# esquematico_trampa.net
KiCad netlist of a schematic drawn in EAGLE
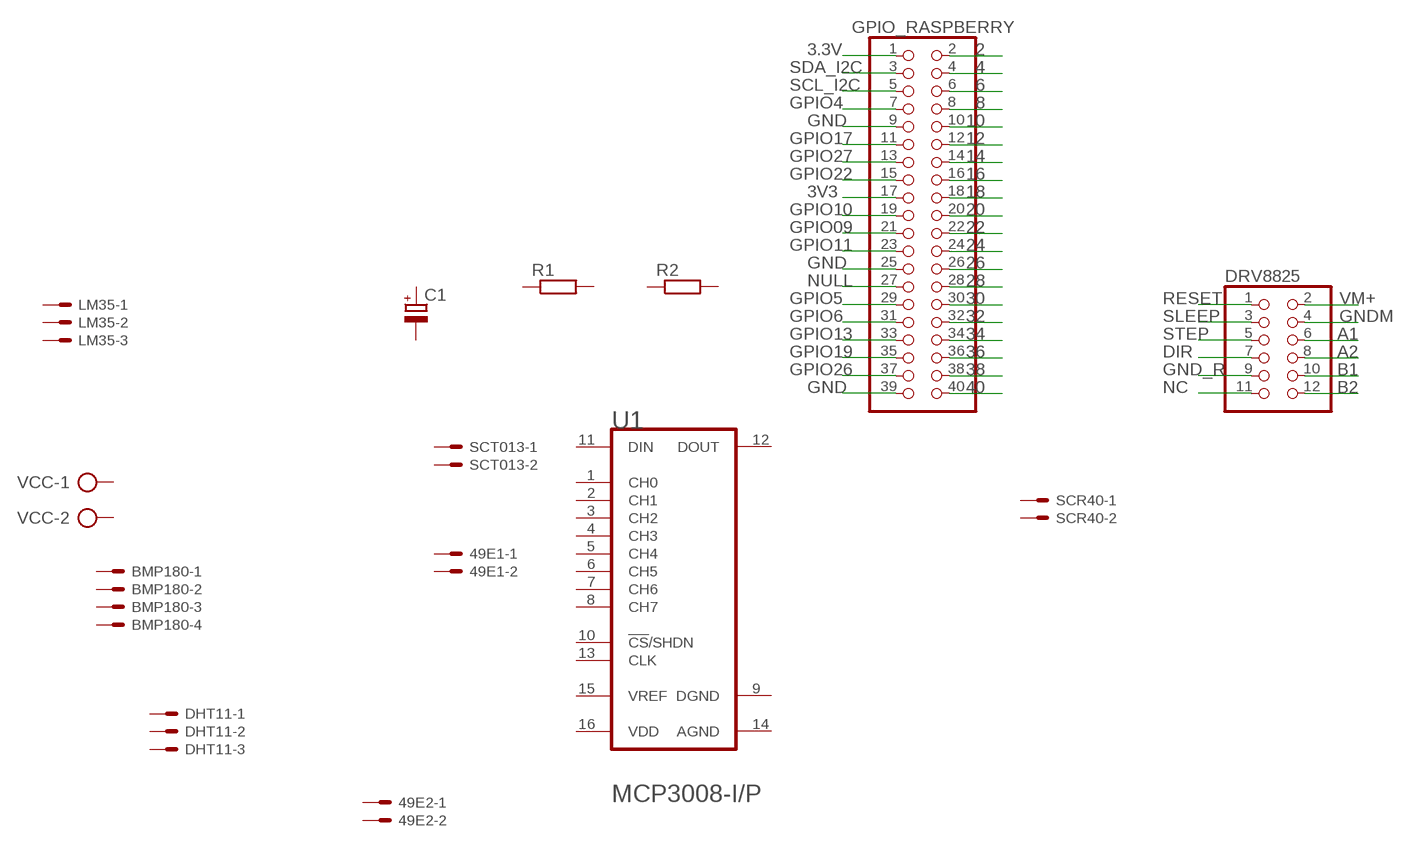
[diagram p0: schematic, sheet 1]

(export (version "E")
  (design (tool "Eeschema 10.0.6"))
  (components
    (comp (ref "49E1")
      (value "22-23-2021")
      (footprint "eagle-import:22-23-2021")
      (fields (field (name "MF") "MOLEX"))
      (libsource (lib "eagle-import") (part "22-23-2021"))
    )
    (comp (ref "49E2")
      (value "22-23-2021")
      (footprint "eagle-import:22-23-2021")
      (fields (field (name "MF") "MOLEX"))
      (libsource (lib "eagle-import") (part "22-23-2021"))
    )
    (comp (ref "BMP180")
      (value "22-23-2041")
      (footprint "eagle-import:22-23-2041")
      (fields (field (name "MF") "MOLEX"))
      (libsource (lib "eagle-import") (part "22-23-2041"))
    )
    (comp (ref "C1")
      (value "CPOL-EUE5-8.5")
      (footprint "eagle-import:E5-8,5")
      (libsource (lib "eagle-import") (part "CPOL-EUE5-8.5"))
    )
    (comp (ref "DHT11")
      (value "22-23-2031")
      (footprint "eagle-import:22-23-2031")
      (fields (field (name "MF") "MOLEX"))
      (libsource (lib "eagle-import") (part "22-23-2031"))
    )
    (comp (ref "DRV8825")
      (value "PINHD-2X6")
      (footprint "eagle-import:2X06")
      (fields (field (name "SPICEPREFIX") "X"))
      (libsource (lib "eagle-import") (part "PINHD-2X6"))
    )
    (comp (ref "GPIO_RASPBERRY")
      (value "PINHD-2X20")
      (footprint "eagle-import:2X20")
      (libsource (lib "eagle-import") (part "PINHD-2X20"))
    )
    (comp (ref "LM35")
      (value "22-23-2031")
      (footprint "eagle-import:22-23-2031")
      (fields (field (name "MF") "MOLEX"))
      (libsource (lib "eagle-import") (part "22-23-2031"))
    )
    (comp (ref "R1")
      (value "R-EU_0309/12")
      (footprint "eagle-import:0309_12")
      (libsource (lib "eagle-import") (part "R-EU_0309/12"))
    )
    (comp (ref "R2")
      (value "R-EU_0309/12")
      (footprint "eagle-import:0309_12")
      (libsource (lib "eagle-import") (part "R-EU_0309/12"))
    )
    (comp (ref "SCR40")
      (value "22-23-2021")
      (footprint "eagle-import:22-23-2021")
      (fields (field (name "MF") "MOLEX"))
      (libsource (lib "eagle-import") (part "22-23-2021"))
    )
    (comp (ref "SCT013")
      (value "22-23-2021")
      (footprint "eagle-import:22-23-2021")
      (fields (field (name "MF") "MOLEX"))
      (libsource (lib "eagle-import") (part "22-23-2021"))
    )
    (comp (ref "U1")
      (value "MICROCHIP_MCP3008-I-PMICROCHIP_MCP3008-I-P_0_0")
      (footprint "eagle-import:MICROCHIP_MCP3008-I-P_0")
      (fields (field (name "MF") "Microchip") (field (name "MPN") "MCP3008-I/P"))
      (libsource (lib "eagle-import") (part "MICROCHIP_MCP3008-I-PMICROCHIP_MCP3008-I-P_0_0"))
    )
    (comp (ref "VCC")
      (value "AK500/2-H")
      (footprint "eagle-import:AK500_2-H")
      (libsource (lib "eagle-import") (part "AK500/2-H"))
    )
  )
  (nets
    (net (code "1") (name "/2") (class "Default")
      (node (ref "GPIO_RASPBERRY") (pin "2") (pinfunction "2_2") (pintype "passive"))
    )
    (net (code "2") (name "/3.3V") (class "Default")
      (node (ref "GPIO_RASPBERRY") (pin "1") (pinfunction "1_1") (pintype "passive"))
    )
    (net (code "3") (name "/3V3") (class "Default")
      (node (ref "GPIO_RASPBERRY") (pin "17") (pinfunction "17_17") (pintype "passive"))
    )
    (net (code "4") (name "/4") (class "Default")
      (node (ref "GPIO_RASPBERRY") (pin "4") (pinfunction "4_4") (pintype "passive"))
    )
    (net (code "5") (name "/6") (class "Default")
      (node (ref "GPIO_RASPBERRY") (pin "6") (pinfunction "6_6") (pintype "passive"))
    )
    (net (code "6") (name "/8") (class "Default")
      (node (ref "GPIO_RASPBERRY") (pin "8") (pinfunction "8_8") (pintype "passive"))
    )
    (net (code "7") (name "/10") (class "Default")
      (node (ref "GPIO_RASPBERRY") (pin "10") (pinfunction "10_10") (pintype "passive"))
    )
    (net (code "8") (name "/12") (class "Default")
      (node (ref "GPIO_RASPBERRY") (pin "12") (pinfunction "12_12") (pintype "passive"))
    )
    (net (code "9") (name "/14") (class "Default")
      (node (ref "GPIO_RASPBERRY") (pin "14") (pinfunction "14_14") (pintype "passive"))
    )
    (net (code "10") (name "/16") (class "Default")
      (node (ref "GPIO_RASPBERRY") (pin "16") (pinfunction "16_16") (pintype "passive"))
    )
    (net (code "11") (name "/18") (class "Default")
      (node (ref "GPIO_RASPBERRY") (pin "18") (pinfunction "18_18") (pintype "passive"))
    )
    (net (code "12") (name "/20") (class "Default")
      (node (ref "GPIO_RASPBERRY") (pin "20") (pinfunction "20_20") (pintype "passive"))
    )
    (net (code "13") (name "/22") (class "Default")
      (node (ref "GPIO_RASPBERRY") (pin "22") (pinfunction "22_22") (pintype "passive"))
    )
    (net (code "14") (name "/24") (class "Default")
      (node (ref "GPIO_RASPBERRY") (pin "24") (pinfunction "24_24") (pintype "passive"))
    )
    (net (code "15") (name "/26") (class "Default")
      (node (ref "GPIO_RASPBERRY") (pin "26") (pinfunction "26_26") (pintype "passive"))
    )
    (net (code "16") (name "/28") (class "Default")
      (node (ref "GPIO_RASPBERRY") (pin "28") (pinfunction "28_28") (pintype "passive"))
    )
    (net (code "17") (name "/30") (class "Default")
      (node (ref "GPIO_RASPBERRY") (pin "30") (pinfunction "30_30") (pintype "passive"))
    )
    (net (code "18") (name "/32") (class "Default")
      (node (ref "GPIO_RASPBERRY") (pin "32") (pinfunction "32_32") (pintype "passive"))
    )
    (net (code "19") (name "/34") (class "Default")
      (node (ref "GPIO_RASPBERRY") (pin "34") (pinfunction "34_34") (pintype "passive"))
    )
    (net (code "20") (name "/36") (class "Default")
      (node (ref "GPIO_RASPBERRY") (pin "36") (pinfunction "36_36") (pintype "passive"))
    )
    (net (code "21") (name "/38") (class "Default")
      (node (ref "GPIO_RASPBERRY") (pin "38") (pinfunction "38_38") (pintype "passive"))
    )
    (net (code "22") (name "/40") (class "Default")
      (node (ref "GPIO_RASPBERRY") (pin "40") (pinfunction "40_40") (pintype "passive"))
    )
    (net (code "23") (name "/A1") (class "Default")
      (node (ref "DRV8825") (pin "6") (pinfunction "6_6") (pintype "passive"))
    )
    (net (code "24") (name "/A2") (class "Default")
      (node (ref "DRV8825") (pin "8") (pinfunction "8_8") (pintype "passive"))
    )
    (net (code "25") (name "/AGND") (class "Default")
      (node (ref "U1") (pin "14") (pinfunction "AGND_14") (pintype "power_in"))
    )
    (net (code "26") (name "/B1") (class "Default")
      (node (ref "DRV8825") (pin "10") (pinfunction "10_10") (pintype "passive"))
    )
    (net (code "27") (name "/B2") (class "Default")
      (node (ref "DRV8825") (pin "12") (pinfunction "12_12") (pintype "passive"))
    )
    (net (code "28") (name "/DGND") (class "Default")
      (node (ref "U1") (pin "9") (pinfunction "DGND_9") (pintype "power_in"))
    )
    (net (code "29") (name "/DIR") (class "Default")
      (node (ref "DRV8825") (pin "7") (pinfunction "7_7") (pintype "passive"))
    )
    (net (code "30") (name "/GND") (class "Default")
      (node (ref "GPIO_RASPBERRY") (pin "25") (pinfunction "25_25") (pintype "passive"))
      (node (ref "GPIO_RASPBERRY") (pin "39") (pinfunction "39_39") (pintype "passive"))
      (node (ref "GPIO_RASPBERRY") (pin "9") (pinfunction "9_9") (pintype "passive"))
    )
    (net (code "31") (name "/GNDM") (class "Default")
      (node (ref "DRV8825") (pin "4") (pinfunction "4_4") (pintype "passive"))
    )
    (net (code "32") (name "/GND_R") (class "Default")
      (node (ref "DRV8825") (pin "9") (pinfunction "9_9") (pintype "passive"))
    )
    (net (code "33") (name "/GPIO4") (class "Default")
      (node (ref "GPIO_RASPBERRY") (pin "7") (pinfunction "7_7") (pintype "passive"))
    )
    (net (code "34") (name "/GPIO5") (class "Default")
      (node (ref "GPIO_RASPBERRY") (pin "29") (pinfunction "29_29") (pintype "passive"))
    )
    (net (code "35") (name "/GPIO6") (class "Default")
      (node (ref "GPIO_RASPBERRY") (pin "31") (pinfunction "31_31") (pintype "passive"))
    )
    (net (code "36") (name "/GPIO09") (class "Default")
      (node (ref "GPIO_RASPBERRY") (pin "21") (pinfunction "21_21") (pintype "passive"))
    )
    (net (code "37") (name "/GPIO10") (class "Default")
      (node (ref "GPIO_RASPBERRY") (pin "19") (pinfunction "19_19") (pintype "passive"))
    )
    (net (code "38") (name "/GPIO11") (class "Default")
      (node (ref "GPIO_RASPBERRY") (pin "23") (pinfunction "23_23") (pintype "passive"))
    )
    (net (code "39") (name "/GPIO13") (class "Default")
      (node (ref "GPIO_RASPBERRY") (pin "33") (pinfunction "33_33") (pintype "passive"))
    )
    (net (code "40") (name "/GPIO17") (class "Default")
      (node (ref "GPIO_RASPBERRY") (pin "11") (pinfunction "11_11") (pintype "passive"))
    )
    (net (code "41") (name "/GPIO19") (class "Default")
      (node (ref "GPIO_RASPBERRY") (pin "35") (pinfunction "35_35") (pintype "passive"))
    )
    (net (code "42") (name "/GPIO22") (class "Default")
      (node (ref "GPIO_RASPBERRY") (pin "15") (pinfunction "15_15") (pintype "passive"))
    )
    (net (code "43") (name "/GPIO26") (class "Default")
      (node (ref "GPIO_RASPBERRY") (pin "37") (pinfunction "37_37") (pintype "passive"))
    )
    (net (code "44") (name "/GPIO27") (class "Default")
      (node (ref "GPIO_RASPBERRY") (pin "13") (pinfunction "13_13") (pintype "passive"))
    )
    (net (code "45") (name "/NC") (class "Default")
      (node (ref "DRV8825") (pin "11") (pinfunction "11_11") (pintype "passive"))
    )
    (net (code "46") (name "/NULL") (class "Default")
      (node (ref "GPIO_RASPBERRY") (pin "27") (pinfunction "27_27") (pintype "passive"))
    )
    (net (code "47") (name "/RESET") (class "Default")
      (node (ref "DRV8825") (pin "1") (pinfunction "1_1") (pintype "passive"))
    )
    (net (code "48") (name "/SCL_I2C") (class "Default")
      (node (ref "GPIO_RASPBERRY") (pin "5") (pinfunction "5_5") (pintype "passive"))
    )
    (net (code "49") (name "/SDA_I2C") (class "Default")
      (node (ref "GPIO_RASPBERRY") (pin "3") (pinfunction "3_3") (pintype "passive"))
    )
    (net (code "50") (name "/SLEEP") (class "Default")
      (node (ref "DRV8825") (pin "3") (pinfunction "3_3") (pintype "passive"))
    )
    (net (code "51") (name "/STEP") (class "Default")
      (node (ref "DRV8825") (pin "5") (pinfunction "5_5") (pintype "passive"))
    )
    (net (code "52") (name "/VDD") (class "Default")
      (node (ref "U1") (pin "16") (pinfunction "VDD_16") (pintype "power_in"))
    )
    (net (code "53") (name "/VM+") (class "Default")
      (node (ref "DRV8825") (pin "2") (pinfunction "2_2") (pintype "passive"))
    )
    (net (code "54") (name "unconnected-(49E1A-S-Pad1)") (class "Default")
      (node (ref "49E1") (pin "1") (pinfunction "S_1") (pintype "passive"))
    )
    (net (code "55") (name "unconnected-(49E1B-S-Pad2)") (class "Default")
      (node (ref "49E1") (pin "2") (pinfunction "S_2") (pintype "passive"))
    )
    (net (code "56") (name "unconnected-(49E2A-S-Pad1)") (class "Default")
      (node (ref "49E2") (pin "1") (pinfunction "S_1") (pintype "passive"))
    )
    (net (code "57") (name "unconnected-(49E2B-S-Pad2)") (class "Default")
      (node (ref "49E2") (pin "2") (pinfunction "S_2") (pintype "passive"))
    )
    (net (code "58") (name "unconnected-(BMP180A-S-Pad1)") (class "Default")
      (node (ref "BMP180") (pin "1") (pinfunction "S_1") (pintype "passive"))
    )
    (net (code "59") (name "unconnected-(BMP180B-S-Pad2)") (class "Default")
      (node (ref "BMP180") (pin "2") (pinfunction "S_2") (pintype "passive"))
    )
    (net (code "60") (name "unconnected-(BMP180C-S-Pad3)") (class "Default")
      (node (ref "BMP180") (pin "3") (pinfunction "S_3") (pintype "passive"))
    )
    (net (code "61") (name "unconnected-(BMP180D-S-Pad4)") (class "Default")
      (node (ref "BMP180") (pin "4") (pinfunction "S_4") (pintype "passive"))
    )
    (net (code "62") (name "unconnected-(C1-Pad+)") (class "Default")
      (node (ref "C1") (pin "+") (pinfunction "+_+") (pintype "passive"))
    )
    (net (code "63") (name "unconnected-(C1-Pad-)") (class "Default")
      (node (ref "C1") (pin "-") (pinfunction "-_-") (pintype "passive"))
    )
    (net (code "64") (name "unconnected-(DHT11A-S-Pad1)") (class "Default")
      (node (ref "DHT11") (pin "1") (pinfunction "S_1") (pintype "passive"))
    )
    (net (code "65") (name "unconnected-(DHT11B-S-Pad2)") (class "Default")
      (node (ref "DHT11") (pin "2") (pinfunction "S_2") (pintype "passive"))
    )
    (net (code "66") (name "unconnected-(DHT11C-S-Pad3)") (class "Default")
      (node (ref "DHT11") (pin "3") (pinfunction "S_3") (pintype "passive"))
    )
    (net (code "67") (name "unconnected-(LM35A-S-Pad1)") (class "Default")
      (node (ref "LM35") (pin "1") (pinfunction "S_1") (pintype "passive"))
    )
    (net (code "68") (name "unconnected-(LM35B-S-Pad2)") (class "Default")
      (node (ref "LM35") (pin "2") (pinfunction "S_2") (pintype "passive"))
    )
    (net (code "69") (name "unconnected-(LM35C-S-Pad3)") (class "Default")
      (node (ref "LM35") (pin "3") (pinfunction "S_3") (pintype "passive"))
    )
    (net (code "70") (name "unconnected-(R1-Pad1)") (class "Default")
      (node (ref "R1") (pin "1") (pinfunction "1_1") (pintype "passive"))
    )
    (net (code "71") (name "unconnected-(R1-Pad2)") (class "Default")
      (node (ref "R1") (pin "2") (pinfunction "2_2") (pintype "passive"))
    )
    (net (code "72") (name "unconnected-(R2-Pad1)") (class "Default")
      (node (ref "R2") (pin "1") (pinfunction "1_1") (pintype "passive"))
    )
    (net (code "73") (name "unconnected-(R2-Pad2)") (class "Default")
      (node (ref "R2") (pin "2") (pinfunction "2_2") (pintype "passive"))
    )
    (net (code "74") (name "unconnected-(SCR40A-S-Pad1)") (class "Default")
      (node (ref "SCR40") (pin "1") (pinfunction "S_1") (pintype "passive"))
    )
    (net (code "75") (name "unconnected-(SCR40B-S-Pad2)") (class "Default")
      (node (ref "SCR40") (pin "2") (pinfunction "S_2") (pintype "passive"))
    )
    (net (code "76") (name "unconnected-(SCT013A-S-Pad1)") (class "Default")
      (node (ref "SCT013") (pin "1") (pinfunction "S_1") (pintype "passive"))
    )
    (net (code "77") (name "unconnected-(SCT013B-S-Pad2)") (class "Default")
      (node (ref "SCT013") (pin "2") (pinfunction "S_2") (pintype "passive"))
    )
    (net (code "78") (name "unconnected-(U1-CH0-Pad1)") (class "Default")
      (node (ref "U1") (pin "1") (pinfunction "CH0_1") (pintype "input"))
    )
    (net (code "79") (name "unconnected-(U1-CH1-Pad2)") (class "Default")
      (node (ref "U1") (pin "2") (pinfunction "CH1_2") (pintype "input"))
    )
    (net (code "80") (name "unconnected-(U1-CH2-Pad3)") (class "Default")
      (node (ref "U1") (pin "3") (pinfunction "CH2_3") (pintype "input"))
    )
    (net (code "81") (name "unconnected-(U1-CH3-Pad4)") (class "Default")
      (node (ref "U1") (pin "4") (pinfunction "CH3_4") (pintype "input"))
    )
    (net (code "82") (name "unconnected-(U1-CH4-Pad5)") (class "Default")
      (node (ref "U1") (pin "5") (pinfunction "CH4_5") (pintype "input"))
    )
    (net (code "83") (name "unconnected-(U1-CH5-Pad6)") (class "Default")
      (node (ref "U1") (pin "6") (pinfunction "CH5_6") (pintype "input"))
    )
    (net (code "84") (name "unconnected-(U1-CH6-Pad7)") (class "Default")
      (node (ref "U1") (pin "7") (pinfunction "CH6_7") (pintype "input"))
    )
    (net (code "85") (name "unconnected-(U1-CH7-Pad8)") (class "Default")
      (node (ref "U1") (pin "8") (pinfunction "CH7_8") (pintype "input"))
    )
    (net (code "86") (name "unconnected-(U1-CLK-Pad13)") (class "Default")
      (node (ref "U1") (pin "13") (pinfunction "CLK_13") (pintype "input"))
    )
    (net (code "87") (name "unconnected-(U1-DIN-Pad11)") (class "Default")
      (node (ref "U1") (pin "11") (pinfunction "DIN_11") (pintype "input"))
    )
    (net (code "88") (name "unconnected-(U1-DOUT-Pad12)") (class "Default")
      (node (ref "U1") (pin "12") (pinfunction "DOUT_12") (pintype "tri_state"))
    )
    (net (code "89") (name "unconnected-(U1-VREF-Pad15)") (class "Default")
      (node (ref "U1") (pin "15") (pinfunction "VREF_15") (pintype "input"))
    )
    (net (code "90") (name "unconnected-(U1-~{CS}{slash}SHDN-Pad10)") (class "Default")
      (node (ref "U1") (pin "10") (pinfunction "~{CS}/SHDN_10") (pintype "input"))
    )
    (net (code "91") (name "unconnected-(VCCA-KL-Pad1)") (class "Default")
      (node (ref "VCC") (pin "1") (pinfunction "KL_1") (pintype "passive"))
    )
    (net (code "92") (name "unconnected-(VCCB-KL-Pad2)") (class "Default")
      (node (ref "VCC") (pin "2") (pinfunction "KL_2") (pintype "passive"))
    )
  )
)
